# dc25-darknet-dialer-eaglev8_2.net
KiCad netlist of a schematic drawn in EAGLE
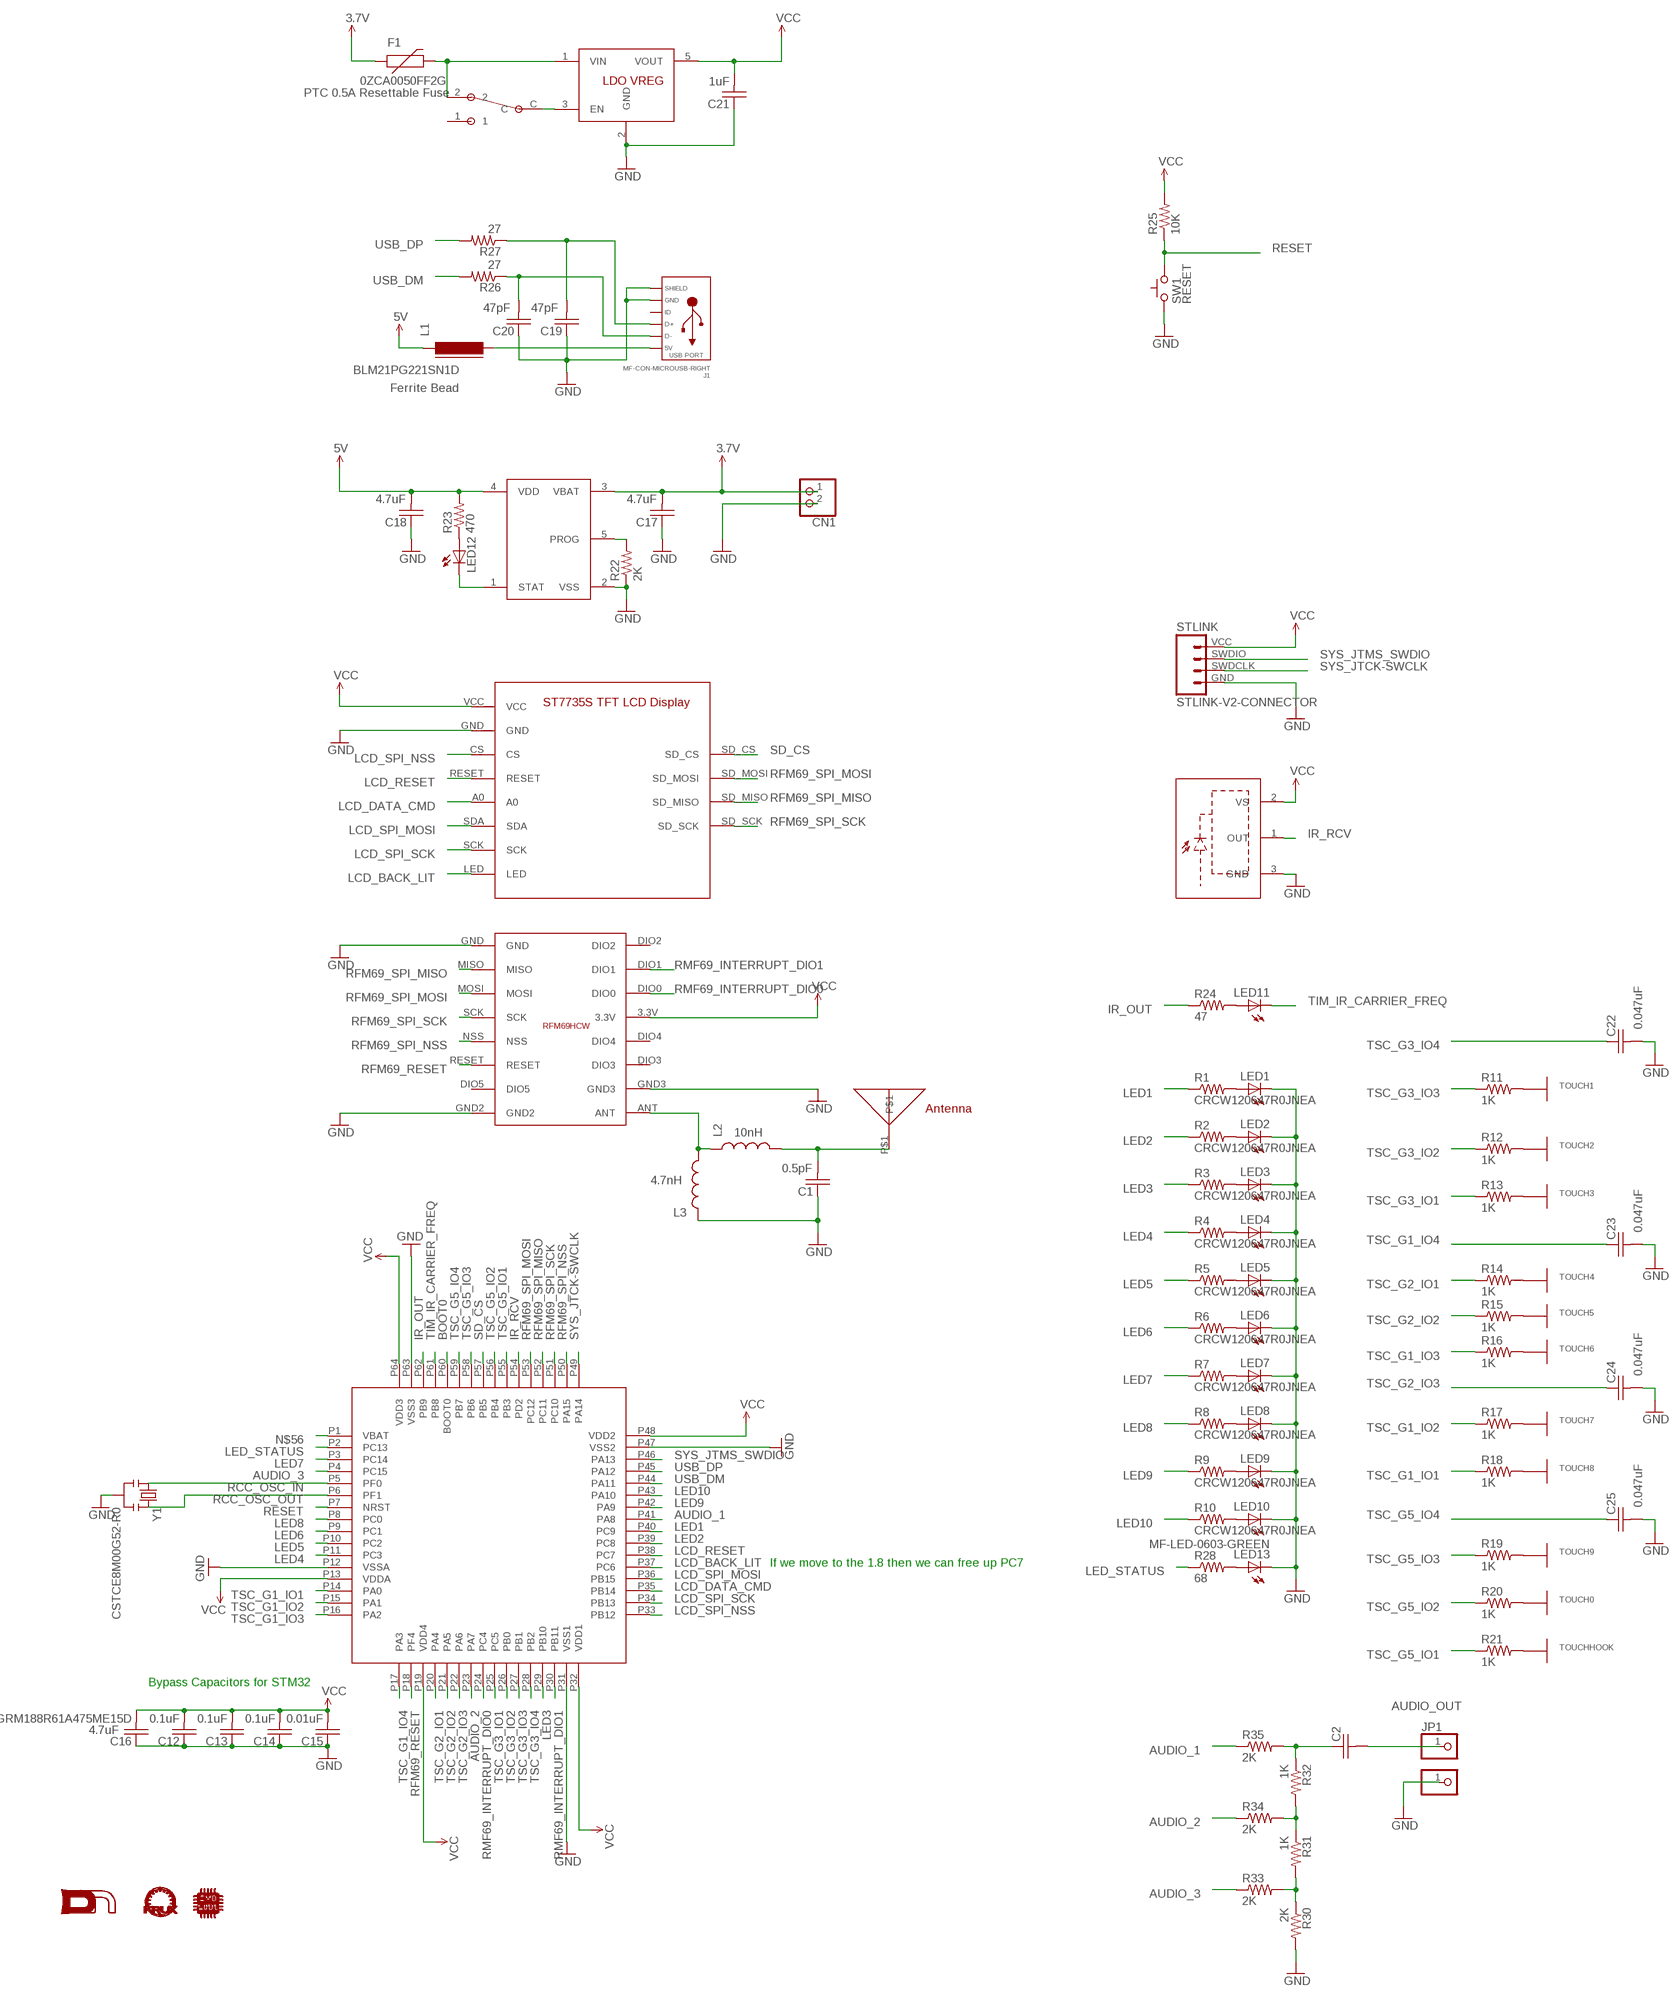
[diagram p0: schematic, sheet 1]

(export (version "E")
  (design (tool "Eeschema 10.0.6"))
  (components
    (comp (ref "C1")
      (value "251R14S0R5BV4T")
      (footprint "eagle-import:C0603")
      (libsource (lib "eagle-import") (part "C-USC0603"))
    )
    (comp (ref "C2")
      (value "GRM188C80G106ME47D")
      (footprint "eagle-import:C0603")
      (libsource (lib "eagle-import") (part "C-USC0603"))
    )
    (comp (ref "C12")
      (value "0.1uF")
      (footprint "eagle-import:C0603")
      (libsource (lib "eagle-import") (part "C-USC0603"))
    )
    (comp (ref "C13")
      (value "0.1uF")
      (footprint "eagle-import:C0603")
      (libsource (lib "eagle-import") (part "C-USC0603"))
    )
    (comp (ref "C14")
      (value "0.1uF")
      (footprint "eagle-import:C0603")
      (libsource (lib "eagle-import") (part "C-USC0603"))
    )
    (comp (ref "C15")
      (value "0.01uF")
      (footprint "eagle-import:C0603")
      (libsource (lib "eagle-import") (part "C-USC0603"))
    )
    (comp (ref "C16")
      (value "GRM188R61A475ME15D")
      (footprint "eagle-import:C0603")
      (libsource (lib "eagle-import") (part "C-USC0603"))
    )
    (comp (ref "C17")
      (value "GRM188R61A475ME15D")
      (footprint "eagle-import:C0603")
      (libsource (lib "eagle-import") (part "C-USC0603"))
    )
    (comp (ref "C18")
      (value "GRM188R61A475ME15D")
      (footprint "eagle-import:C0603")
      (libsource (lib "eagle-import") (part "C-USC0603"))
    )
    (comp (ref "C19")
      (value "C0603C470J3GACTU")
      (footprint "eagle-import:C0603")
      (libsource (lib "eagle-import") (part "C-USC0603"))
    )
    (comp (ref "C20")
      (value "C0603C470J3GACTU")
      (footprint "eagle-import:C0603")
      (libsource (lib "eagle-import") (part "C-USC0603"))
    )
    (comp (ref "C21")
      (value "1uF")
      (footprint "eagle-import:C0603")
      (libsource (lib "eagle-import") (part "C-USC0603"))
    )
    (comp (ref "C22")
      (value "C0603C473J3RACAUTO")
      (footprint "eagle-import:C0603")
      (libsource (lib "eagle-import") (part "C-USC0603"))
    )
    (comp (ref "C23")
      (value "C0603C473J3RACAUTO")
      (footprint "eagle-import:C0603")
      (libsource (lib "eagle-import") (part "C-USC0603"))
    )
    (comp (ref "C24")
      (value "C0603C473J3RACAUTO")
      (footprint "eagle-import:C0603")
      (libsource (lib "eagle-import") (part "C-USC0603"))
    )
    (comp (ref "C25")
      (value "C0603C473J3RACAUTO")
      (footprint "eagle-import:C0603")
      (libsource (lib "eagle-import") (part "C-USC0603"))
    )
    (comp (ref "CN1")
      (value "JST_2PIN-THM-RA")
      (footprint "eagle-import:JST-PH-2-THM-RA")
      (libsource (lib "eagle-import") (part "JST_2PIN-THM-RA"))
    )
    (comp (ref "F1")
      (value "0ZCA0050FF2G")
      (footprint "eagle-import:PTC-1206")
      (libsource (lib "eagle-import") (part "PTCSMD"))
    )
    (comp (ref "J1")
      (value "MF-CON-MICROUSB-RIGHT")
      (footprint "eagle-import:MICROUSB-RIGHT")
      (fields (field (name "HOUSEPART") "YES"))
      (libsource (lib "eagle-import") (part "USB_MICRO_RIGHT"))
    )
    (comp (ref "JP1")
      (value "PINHD-1X1CB")
      (footprint "eagle-import:1X01-CLEANBIG")
      (libsource (lib "eagle-import") (part "PINHD-1X1CB"))
    )
    (comp (ref "JP2")
      (value "PINHD-1X1CB")
      (footprint "eagle-import:1X01-CLEANBIG")
      (libsource (lib "eagle-import") (part "PINHD-1X1CB"))
    )
    (comp (ref "L1")
      (value "BLM21PG221SN1D")
      (footprint "eagle-import:FB603")
      (libsource (lib "eagle-import") (part "FERRITE-0603"))
    )
    (comp (ref "L2")
      (value "CI160808-10NJ")
      (footprint "eagle-import:0603")
      (libsource (lib "eagle-import") (part "INDUCTOR0603"))
    )
    (comp (ref "L3")
      (value "CI160808-4N7D")
      (footprint "eagle-import:0603")
      (libsource (lib "eagle-import") (part "INDUCTOR0603"))
    )
    (comp (ref "LED1")
      (value "LEDREVERSEMOUNT_NOPASTE")
      (footprint "eagle-import:GULLWING_LED_NOPASTE")
      (libsource (lib "eagle-import") (part "LEDREVERSEMOUNT_NOPASTE"))
    )
    (comp (ref "LED2")
      (value "LEDREVERSEMOUNT_NOPASTE")
      (footprint "eagle-import:GULLWING_LED_NOPASTE")
      (libsource (lib "eagle-import") (part "LEDREVERSEMOUNT_NOPASTE"))
    )
    (comp (ref "LED3")
      (value "LEDREVERSEMOUNT_NOPASTE")
      (footprint "eagle-import:GULLWING_LED_NOPASTE")
      (libsource (lib "eagle-import") (part "LEDREVERSEMOUNT_NOPASTE"))
    )
    (comp (ref "LED4")
      (value "LEDREVERSEMOUNT_NOPASTE")
      (footprint "eagle-import:GULLWING_LED_NOPASTE")
      (libsource (lib "eagle-import") (part "LEDREVERSEMOUNT_NOPASTE"))
    )
    (comp (ref "LED5")
      (value "LEDREVERSEMOUNT_NOPASTE")
      (footprint "eagle-import:GULLWING_LED_NOPASTE")
      (libsource (lib "eagle-import") (part "LEDREVERSEMOUNT_NOPASTE"))
    )
    (comp (ref "LED6")
      (value "LEDREVERSEMOUNT_NOPASTE")
      (footprint "eagle-import:GULLWING_LED_NOPASTE")
      (libsource (lib "eagle-import") (part "LEDREVERSEMOUNT_NOPASTE"))
    )
    (comp (ref "LED7")
      (value "LEDREVERSEMOUNT_NOPASTE")
      (footprint "eagle-import:GULLWING_LED_NOPASTE")
      (libsource (lib "eagle-import") (part "LEDREVERSEMOUNT_NOPASTE"))
    )
    (comp (ref "LED8")
      (value "LEDREVERSEMOUNT_NOPASTE")
      (footprint "eagle-import:GULLWING_LED_NOPASTE")
      (libsource (lib "eagle-import") (part "LEDREVERSEMOUNT_NOPASTE"))
    )
    (comp (ref "LED9")
      (value "LEDREVERSEMOUNT_NOPASTE")
      (footprint "eagle-import:GULLWING_LED_NOPASTE")
      (libsource (lib "eagle-import") (part "LEDREVERSEMOUNT_NOPASTE"))
    )
    (comp (ref "LED10")
      (value "LEDREVERSEMOUNT_NOPASTE")
      (footprint "eagle-import:GULLWING_LED_NOPASTE")
      (libsource (lib "eagle-import") (part "LEDREVERSEMOUNT_NOPASTE"))
    )
    (comp (ref "LED11")
      (value "LED5MM")
      (footprint "eagle-import:LED5MM")
      (libsource (lib "eagle-import") (part "LED5MM"))
    )
    (comp (ref "LED12")
      (value "MF-LED-0603-GREEN")
      (footprint "eagle-import:LED-0603")
      (libsource (lib "eagle-import") (part "LED0603"))
    )
    (comp (ref "LED13")
      (value "MF-LED-0603-GREEN")
      (footprint "eagle-import:LED-0603")
      (libsource (lib "eagle-import") (part "LED0603"))
    )
    (comp (ref "R1")
      (value "CRCW120647R0JNEA")
      (footprint "eagle-import:1206")
      (libsource (lib "eagle-import") (part "RESISTOR1206"))
    )
    (comp (ref "R2")
      (value "CRCW120647R0JNEA")
      (footprint "eagle-import:1206")
      (libsource (lib "eagle-import") (part "RESISTOR1206"))
    )
    (comp (ref "R3")
      (value "CRCW120647R0JNEA")
      (footprint "eagle-import:1206")
      (libsource (lib "eagle-import") (part "RESISTOR1206"))
    )
    (comp (ref "R4")
      (value "CRCW120647R0JNEA")
      (footprint "eagle-import:1206")
      (libsource (lib "eagle-import") (part "RESISTOR1206"))
    )
    (comp (ref "R5")
      (value "CRCW120647R0JNEA")
      (footprint "eagle-import:1206")
      (libsource (lib "eagle-import") (part "RESISTOR1206"))
    )
    (comp (ref "R6")
      (value "CRCW120647R0JNEA")
      (footprint "eagle-import:1206")
      (libsource (lib "eagle-import") (part "RESISTOR1206"))
    )
    (comp (ref "R7")
      (value "CRCW120647R0JNEA")
      (footprint "eagle-import:1206")
      (libsource (lib "eagle-import") (part "RESISTOR1206"))
    )
    (comp (ref "R8")
      (value "CRCW120647R0JNEA")
      (footprint "eagle-import:1206")
      (libsource (lib "eagle-import") (part "RESISTOR1206"))
    )
    (comp (ref "R9")
      (value "CRCW120647R0JNEA")
      (footprint "eagle-import:1206")
      (libsource (lib "eagle-import") (part "RESISTOR1206"))
    )
    (comp (ref "R10")
      (value "CRCW120647R0JNEA")
      (footprint "eagle-import:1206")
      (libsource (lib "eagle-import") (part "RESISTOR1206"))
    )
    (comp (ref "R11")
      (value "1K")
      (footprint "eagle-import:0603-RES")
      (libsource (lib "eagle-import") (part "RESISTOR0603-RES"))
    )
    (comp (ref "R12")
      (value "1K")
      (footprint "eagle-import:0603-RES")
      (libsource (lib "eagle-import") (part "RESISTOR0603-RES"))
    )
    (comp (ref "R13")
      (value "1K")
      (footprint "eagle-import:0603-RES")
      (libsource (lib "eagle-import") (part "RESISTOR0603-RES"))
    )
    (comp (ref "R14")
      (value "1K")
      (footprint "eagle-import:0603-RES")
      (libsource (lib "eagle-import") (part "RESISTOR0603-RES"))
    )
    (comp (ref "R15")
      (value "1K")
      (footprint "eagle-import:0603-RES")
      (libsource (lib "eagle-import") (part "RESISTOR0603-RES"))
    )
    (comp (ref "R16")
      (value "1K")
      (footprint "eagle-import:0603-RES")
      (libsource (lib "eagle-import") (part "RESISTOR0603-RES"))
    )
    (comp (ref "R17")
      (value "1K")
      (footprint "eagle-import:0603-RES")
      (libsource (lib "eagle-import") (part "RESISTOR0603-RES"))
    )
    (comp (ref "R18")
      (value "1K")
      (footprint "eagle-import:0603-RES")
      (libsource (lib "eagle-import") (part "RESISTOR0603-RES"))
    )
    (comp (ref "R19")
      (value "1K")
      (footprint "eagle-import:0603-RES")
      (libsource (lib "eagle-import") (part "RESISTOR0603-RES"))
    )
    (comp (ref "R20")
      (value "1K")
      (footprint "eagle-import:0603-RES")
      (libsource (lib "eagle-import") (part "RESISTOR0603-RES"))
    )
    (comp (ref "R21")
      (value "1K")
      (footprint "eagle-import:0603-RES")
      (libsource (lib "eagle-import") (part "RESISTOR0603-RES"))
    )
    (comp (ref "R22")
      (value "2K")
      (footprint "eagle-import:0603-RES")
      (libsource (lib "eagle-import") (part "RESISTOR0603-RES"))
    )
    (comp (ref "R23")
      (value "470")
      (footprint "eagle-import:0603-RES")
      (libsource (lib "eagle-import") (part "RESISTOR0603-RES"))
    )
    (comp (ref "R24")
      (value "47")
      (footprint "eagle-import:0207_7")
      (libsource (lib "eagle-import") (part "R-US_0207/7"))
    )
    (comp (ref "R25")
      (value "10K")
      (footprint "eagle-import:0603-RES")
      (libsource (lib "eagle-import") (part "RESISTOR0603-RES"))
    )
    (comp (ref "R26")
      (value "27")
      (footprint "eagle-import:0603-RES")
      (libsource (lib "eagle-import") (part "RESISTOR0603-RES"))
    )
    (comp (ref "R27")
      (value "27")
      (footprint "eagle-import:0603-RES")
      (libsource (lib "eagle-import") (part "RESISTOR0603-RES"))
    )
    (comp (ref "R28")
      (value "68")
      (footprint "eagle-import:0603-RES")
      (libsource (lib "eagle-import") (part "RESISTOR0603-RES"))
    )
    (comp (ref "R30")
      (value "2K")
      (footprint "eagle-import:0603-RES")
      (libsource (lib "eagle-import") (part "RESISTOR0603-RES"))
    )
    (comp (ref "R31")
      (value "1K")
      (footprint "eagle-import:0603-RES")
      (libsource (lib "eagle-import") (part "RESISTOR0603-RES"))
    )
    (comp (ref "R32")
      (value "1K")
      (footprint "eagle-import:0603-RES")
      (libsource (lib "eagle-import") (part "RESISTOR0603-RES"))
    )
    (comp (ref "R33")
      (value "2K")
      (footprint "eagle-import:0603-RES")
      (libsource (lib "eagle-import") (part "RESISTOR0603-RES"))
    )
    (comp (ref "R34")
      (value "2K")
      (footprint "eagle-import:0603-RES")
      (libsource (lib "eagle-import") (part "RESISTOR0603-RES"))
    )
    (comp (ref "R35")
      (value "2K")
      (footprint "eagle-import:0603-RES")
      (libsource (lib "eagle-import") (part "RESISTOR0603-RES"))
    )
    (comp (ref "STLINK")
      (value "STLINK-V2-CONNECTOR")
      (footprint "eagle-import:1X04")
      (libsource (lib "eagle-import") (part "STLINK-V2-CONNECTOR"))
    )
    (comp (ref "SW1")
      (value "RESET")
      (footprint "eagle-import:TACTILE-2PIN-NARROW")
      (libsource (lib "eagle-import") (part "SWITCH_TACTILETACTILE-2PIN-NARROW"))
    )
    (comp (ref "TOUCH0")
      (value "CAP_TOUCH0")
      (footprint "eagle-import:CAP_TOUCH_PAD_0")
      (libsource (lib "eagle-import") (part "CAP_TOUCH0"))
    )
    (comp (ref "TOUCH1")
      (value "CAP_TOUCH1")
      (footprint "eagle-import:CAP_TOUCH_PAD_1")
      (libsource (lib "eagle-import") (part "CAP_TOUCH1"))
    )
    (comp (ref "TOUCH2")
      (value "CAP_TOUCH2")
      (footprint "eagle-import:CAP_TOUCH_PAD_2")
      (libsource (lib "eagle-import") (part "CAP_TOUCH2"))
    )
    (comp (ref "TOUCH3")
      (value "CAP_TOUCH3")
      (footprint "eagle-import:CAP_TOUCH_PAD_3")
      (libsource (lib "eagle-import") (part "CAP_TOUCH3"))
    )
    (comp (ref "TOUCH4")
      (value "CAP_TOUCH4")
      (footprint "eagle-import:CAP_TOUCH_PAD_4")
      (libsource (lib "eagle-import") (part "CAP_TOUCH4"))
    )
    (comp (ref "TOUCH5")
      (value "CAP_TOUCH5")
      (footprint "eagle-import:CAP_TOUCH_PAD_5")
      (libsource (lib "eagle-import") (part "CAP_TOUCH5"))
    )
    (comp (ref "TOUCH6")
      (value "CAP_TOUCH6")
      (footprint "eagle-import:CAP_TOUCH_PAD_6")
      (libsource (lib "eagle-import") (part "CAP_TOUCH6"))
    )
    (comp (ref "TOUCH7")
      (value "CAP_TOUCH7")
      (footprint "eagle-import:CAP_TOUCH_PAD_7")
      (libsource (lib "eagle-import") (part "CAP_TOUCH7"))
    )
    (comp (ref "TOUCH8")
      (value "CAP_TOUCH8")
      (footprint "eagle-import:CAP_TOUCH_PAD_8")
      (libsource (lib "eagle-import") (part "CAP_TOUCH8"))
    )
    (comp (ref "TOUCH9")
      (value "CAP_TOUCH9")
      (footprint "eagle-import:CAP_TOUCH_PAD_9")
      (libsource (lib "eagle-import") (part "CAP_TOUCH9"))
    )
    (comp (ref "TOUCHHOOK")
      (value "CAP_TOUCHHOOK")
      (footprint "eagle-import:CAP_TOUCH_PAD_HOOK")
      (libsource (lib "eagle-import") (part "CAP_TOUCHHOOK"))
    )
    (comp (ref "U$1")
      (value "DN_LOGODC25")
      (footprint "eagle-import:DARKNET_LOGO_DC25")
      (libsource (lib "eagle-import") (part "DN_LOGODC25"))
    )
    (comp (ref "U$2")
      (value "STM32F302RBT6")
      (footprint "eagle-import:LQFP64")
      (libsource (lib "eagle-import") (part "STM32F302XC"))
    )
    (comp (ref "U$11")
      (value "SWITCH_SPDT")
      (footprint "eagle-import:SPDT_SSAJ120100")
      (libsource (lib "eagle-import") (part "SWITCH_SPDT"))
    )
    (comp (ref "U$12")
      (value "KRUX_LOGO")
      (footprint "eagle-import:KRUX_LOGO")
      (libsource (lib "eagle-import") (part "KRUX_LOGO"))
    )
    (comp (ref "U$15")
      (value "RFM69HCWRFM69HCWSMDNOPASTE")
      (footprint "eagle-import:16PIN-PCB-SMD-NOPASTE")
      (libsource (lib "eagle-import") (part "RFM69HCWRFM69HCWSMDNOPASTE"))
    )
    (comp (ref "U$21")
      (value "0915AT43A0026E")
      (footprint "eagle-import:CHIP_ANTENNA_1.8X8MM")
      (libsource (lib "eagle-import") (part "CHIP_ANTENNA"))
    )
    (comp (ref "U$22")
      (value "ST7735S_LCD_MODULE")
      (footprint "eagle-import:ST7735S_LCD_DISPLAY")
      (libsource (lib "eagle-import") (part "ST7735S_LCD_MODULE"))
    )
    (comp (ref "U$23")
      (value "CMD_C0DE_LOGO")
      (footprint "eagle-import:CMD_C0DE_LOGO")
      (libsource (lib "eagle-import") (part "CMD_C0DE_LOGO"))
    )
    (comp (ref "U1")
      (value "BU33SD5WG-TR")
      (footprint "eagle-import:SOT23-5")
      (libsource (lib "eagle-import") (part "TLV702"))
    )
    (comp (ref "U2")
      (value "MCP73831T-5ACI/OT")
      (footprint "eagle-import:SOT23-5")
      (libsource (lib "eagle-import") (part "DS21984E"))
    )
    (comp (ref "U3")
      (value "SOP22FLAT")
      (footprint "eagle-import:IR-MODULE_FLAT")
      (libsource (lib "eagle-import") (part "SOP22FLAT"))
    )
    (comp (ref "Y1")
      (value "CSTCE8M00G52-R0")
      (footprint "eagle-import:RESONATOR-SMD")
      (libsource (lib "eagle-import") (part "RESONATORSMD"))
    )
  )
  (nets
    (net (code "1") (name "/AUDIO_1") (class "Default")
      (node (ref "R35") (pin "1") (pinfunction "1_1") (pintype "passive"))
      (node (ref "U$2") (pin "P41") (pinfunction "PA8_P41") (pintype "bidirectional"))
    )
    (net (code "2") (name "/AUDIO_2") (class "Default")
      (node (ref "R34") (pin "1") (pinfunction "1_1") (pintype "passive"))
      (node (ref "U$2") (pin "P23") (pinfunction "PA7_P23") (pintype "bidirectional"))
    )
    (net (code "3") (name "/AUDIO_3") (class "Default")
      (node (ref "R33") (pin "1") (pinfunction "1_1") (pintype "passive"))
      (node (ref "U$2") (pin "P4") (pinfunction "PC15_P4") (pintype "bidirectional"))
    )
    (net (code "4") (name "/AUDIO_OUT") (class "Default")
      (node (ref "C2") (pin "2") (pinfunction "2_2") (pintype "passive"))
      (node (ref "JP1") (pin "1") (pinfunction "1_1") (pintype "passive"))
    )
    (net (code "5") (name "/BOOT0") (class "Default")
      (node (ref "U$2") (pin "P60") (pinfunction "BOOT0_P60") (pintype "bidirectional"))
    )
    (net (code "6") (name "/IR_OUT") (class "Default")
      (node (ref "R24") (pin "1") (pinfunction "1_1") (pintype "passive"))
      (node (ref "U$2") (pin "P62") (pinfunction "PB9_P62") (pintype "bidirectional"))
    )
    (net (code "7") (name "/IR_RCV") (class "Default")
      (node (ref "U$2") (pin "P54") (pinfunction "PD2_P54") (pintype "bidirectional"))
      (node (ref "U3") (pin "1") (pinfunction "OUT_1") (pintype "bidirectional"))
    )
    (net (code "8") (name "/LCD_BACK_LIT") (class "Default")
      (node (ref "U$2") (pin "P37") (pinfunction "PC6_P37") (pintype "bidirectional"))
      (node (ref "U$22") (pin "LED") (pinfunction "LED_LED") (pintype "bidirectional"))
    )
    (net (code "9") (name "/LCD_DATA_CMD") (class "Default")
      (node (ref "U$2") (pin "P35") (pinfunction "PB14_P35") (pintype "bidirectional"))
      (node (ref "U$22") (pin "A0") (pinfunction "A0_A0") (pintype "bidirectional"))
    )
    (net (code "10") (name "/LCD_RESET") (class "Default")
      (node (ref "U$2") (pin "P38") (pinfunction "PC7_P38") (pintype "bidirectional"))
      (node (ref "U$22") (pin "RESET") (pinfunction "RESET_RESET") (pintype "bidirectional"))
    )
    (net (code "11") (name "/LCD_SPI_MOSI") (class "Default")
      (node (ref "U$2") (pin "P36") (pinfunction "PB15_P36") (pintype "bidirectional"))
      (node (ref "U$22") (pin "SDA") (pinfunction "SDA_SDA") (pintype "bidirectional"))
    )
    (net (code "12") (name "/LCD_SPI_NSS") (class "Default")
      (node (ref "U$2") (pin "P33") (pinfunction "PB12_P33") (pintype "bidirectional"))
      (node (ref "U$22") (pin "CS") (pinfunction "CS_CS") (pintype "bidirectional"))
    )
    (net (code "13") (name "/LCD_SPI_SCK") (class "Default")
      (node (ref "U$2") (pin "P34") (pinfunction "PB13_P34") (pintype "bidirectional"))
      (node (ref "U$22") (pin "SCK") (pinfunction "SCK_SCK") (pintype "bidirectional"))
    )
    (net (code "14") (name "/LED1") (class "Default")
      (node (ref "R1") (pin "1") (pinfunction "1_1") (pintype "passive"))
      (node (ref "U$2") (pin "P40") (pinfunction "PC9_P40") (pintype "bidirectional"))
    )
    (net (code "15") (name "/LED2") (class "Default")
      (node (ref "R2") (pin "1") (pinfunction "1_1") (pintype "passive"))
      (node (ref "U$2") (pin "P39") (pinfunction "PC8_P39") (pintype "bidirectional"))
    )
    (net (code "16") (name "/LED3") (class "Default")
      (node (ref "R3") (pin "1") (pinfunction "1_1") (pintype "passive"))
      (node (ref "U$2") (pin "P29") (pinfunction "PB10_P29") (pintype "bidirectional"))
    )
    (net (code "17") (name "/LED4") (class "Default")
      (node (ref "R4") (pin "1") (pinfunction "1_1") (pintype "passive"))
      (node (ref "U$2") (pin "P11") (pinfunction "PC3_P11") (pintype "bidirectional"))
    )
    (net (code "18") (name "/LED5") (class "Default")
      (node (ref "R5") (pin "1") (pinfunction "1_1") (pintype "passive"))
      (node (ref "U$2") (pin "P10") (pinfunction "PC2_P10") (pintype "bidirectional"))
    )
    (net (code "19") (name "/LED6") (class "Default")
      (node (ref "R6") (pin "1") (pinfunction "1_1") (pintype "passive"))
      (node (ref "U$2") (pin "P9") (pinfunction "PC1_P9") (pintype "bidirectional"))
    )
    (net (code "20") (name "/LED7") (class "Default")
      (node (ref "R7") (pin "1") (pinfunction "1_1") (pintype "passive"))
      (node (ref "U$2") (pin "P3") (pinfunction "PC14_P3") (pintype "bidirectional"))
    )
    (net (code "21") (name "/LED8") (class "Default")
      (node (ref "R8") (pin "1") (pinfunction "1_1") (pintype "passive"))
      (node (ref "U$2") (pin "P8") (pinfunction "PC0_P8") (pintype "bidirectional"))
    )
    (net (code "22") (name "/LED9") (class "Default")
      (node (ref "R9") (pin "1") (pinfunction "1_1") (pintype "passive"))
      (node (ref "U$2") (pin "P42") (pinfunction "PA9_P42") (pintype "bidirectional"))
    )
    (net (code "23") (name "/LED10") (class "Default")
      (node (ref "R10") (pin "1") (pinfunction "1_1") (pintype "passive"))
      (node (ref "U$2") (pin "P43") (pinfunction "PA10_P43") (pintype "bidirectional"))
    )
    (net (code "24") (name "/LED_STATUS") (class "Default")
      (node (ref "R28") (pin "1") (pinfunction "1_1") (pintype "passive"))
      (node (ref "U$2") (pin "P2") (pinfunction "PC13_P2") (pintype "bidirectional"))
    )
    (net (code "25") (name "/N$56") (class "Default")
      (node (ref "U$2") (pin "P1") (pinfunction "VBAT_P1") (pintype "bidirectional"))
    )
    (net (code "26") (name "/RCC_OSC_IN") (class "Default")
      (node (ref "U$2") (pin "P5") (pinfunction "PF0_P5") (pintype "bidirectional"))
      (node (ref "Y1") (pin "1") (pinfunction "1_1") (pintype "passive"))
    )
    (net (code "27") (name "/RCC_OSC_OUT") (class "Default")
      (node (ref "U$2") (pin "P6") (pinfunction "PF1_P6") (pintype "bidirectional"))
      (node (ref "Y1") (pin "3") (pinfunction "3_3") (pintype "passive"))
    )
    (net (code "28") (name "/RESET") (class "Default")
      (node (ref "R25") (pin "1") (pinfunction "1_1") (pintype "passive"))
      (node (ref "SW1") (pin "P$1") (pinfunction "A_P$1") (pintype "passive"))
      (node (ref "U$2") (pin "P7") (pinfunction "NRST_P7") (pintype "bidirectional"))
    )
    (net (code "29") (name "/RFM69_RESET") (class "Default")
      (node (ref "U$15") (pin "RESET") (pinfunction "RESET_RESET") (pintype "bidirectional"))
      (node (ref "U$2") (pin "P18") (pinfunction "PF4_P18") (pintype "bidirectional"))
    )
    (net (code "30") (name "/RFM69_SPI_MISO") (class "Default")
      (node (ref "U$15") (pin "MISO") (pinfunction "MISO_MISO") (pintype "bidirectional"))
      (node (ref "U$2") (pin "P52") (pinfunction "PC11_P52") (pintype "bidirectional"))
      (node (ref "U$22") (pin "SD_MISO") (pinfunction "SD_MISO_SD_MISO") (pintype "bidirectional"))
    )
    (net (code "31") (name "/RFM69_SPI_MOSI") (class "Default")
      (node (ref "U$15") (pin "MOSI") (pinfunction "MOSI_MOSI") (pintype "bidirectional"))
      (node (ref "U$2") (pin "P53") (pinfunction "PC12_P53") (pintype "bidirectional"))
      (node (ref "U$22") (pin "SD_MOSI") (pinfunction "SD_MOSI_SD_MOSI") (pintype "bidirectional"))
    )
    (net (code "32") (name "/RFM69_SPI_NSS") (class "Default")
      (node (ref "U$15") (pin "NSS") (pinfunction "NSS_NSS") (pintype "bidirectional"))
      (node (ref "U$2") (pin "P50") (pinfunction "PA15_P50") (pintype "bidirectional"))
    )
    (net (code "33") (name "/RFM69_SPI_SCK") (class "Default")
      (node (ref "U$15") (pin "SCK") (pinfunction "SCK_SCK") (pintype "bidirectional"))
      (node (ref "U$2") (pin "P51") (pinfunction "PC10_P51") (pintype "bidirectional"))
      (node (ref "U$22") (pin "SD_SCK") (pinfunction "SD_SCK_SD_SCK") (pintype "bidirectional"))
    )
    (net (code "34") (name "/RMF69_INTERRUPT_DIO0") (class "Default")
      (node (ref "U$15") (pin "DIO0") (pinfunction "DIO0_DIO0") (pintype "bidirectional"))
      (node (ref "U$2") (pin "P24") (pinfunction "PC4_P24") (pintype "bidirectional"))
    )
    (net (code "35") (name "/RMF69_INTERRUPT_DIO1") (class "Default")
      (node (ref "U$15") (pin "DIO1") (pinfunction "DIO1_DIO1") (pintype "bidirectional"))
      (node (ref "U$2") (pin "P30") (pinfunction "PB11_P30") (pintype "bidirectional"))
    )
    (net (code "36") (name "/SD_CS") (class "Default")
      (node (ref "U$2") (pin "P57") (pinfunction "PB5_P57") (pintype "bidirectional"))
      (node (ref "U$22") (pin "SD_CS") (pinfunction "SD_CS_SD_CS") (pintype "bidirectional"))
    )
    (net (code "37") (name "/SYS_JTCK-SWCLK") (class "Default")
      (node (ref "STLINK") (pin "SWDCLK") (pinfunction "SWDCLK_SWDCLK") (pintype "input"))
      (node (ref "U$2") (pin "P49") (pinfunction "PA14_P49") (pintype "bidirectional"))
    )
    (net (code "38") (name "/SYS_JTMS_SWDIO") (class "Default")
      (node (ref "STLINK") (pin "SWDIO") (pinfunction "SWDIO_SWDIO") (pintype "bidirectional"))
      (node (ref "U$2") (pin "P46") (pinfunction "PA13_P46") (pintype "bidirectional"))
    )
    (net (code "39") (name "/TIM_IR_CARRIER_FREQ") (class "Default")
      (node (ref "LED11") (pin "K") (pinfunction "C_K") (pintype "output"))
      (node (ref "U$2") (pin "P61") (pinfunction "PB8_P61") (pintype "bidirectional"))
    )
    (net (code "40") (name "/TSC_G1_IO1") (class "Default")
      (node (ref "R18") (pin "1") (pinfunction "1_1") (pintype "passive"))
      (node (ref "U$2") (pin "P14") (pinfunction "PA0_P14") (pintype "bidirectional"))
    )
    (net (code "41") (name "/TSC_G1_IO2") (class "Default")
      (node (ref "R17") (pin "1") (pinfunction "1_1") (pintype "passive"))
      (node (ref "U$2") (pin "P15") (pinfunction "PA1_P15") (pintype "bidirectional"))
    )
    (net (code "42") (name "/TSC_G1_IO3") (class "Default")
      (node (ref "R16") (pin "1") (pinfunction "1_1") (pintype "passive"))
      (node (ref "U$2") (pin "P16") (pinfunction "PA2_P16") (pintype "bidirectional"))
    )
    (net (code "43") (name "/TSC_G1_IO4") (class "Default")
      (node (ref "C23") (pin "1") (pinfunction "1_1") (pintype "passive"))
      (node (ref "U$2") (pin "P17") (pinfunction "PA3_P17") (pintype "bidirectional"))
    )
    (net (code "44") (name "/TSC_G2_IO1") (class "Default")
      (node (ref "R14") (pin "1") (pinfunction "1_1") (pintype "passive"))
      (node (ref "U$2") (pin "P20") (pinfunction "PA4_P20") (pintype "bidirectional"))
    )
    (net (code "45") (name "/TSC_G2_IO2") (class "Default")
      (node (ref "R15") (pin "1") (pinfunction "1_1") (pintype "passive"))
      (node (ref "U$2") (pin "P21") (pinfunction "PA5_P21") (pintype "bidirectional"))
    )
    (net (code "46") (name "/TSC_G2_IO3") (class "Default")
      (node (ref "C24") (pin "1") (pinfunction "1_1") (pintype "passive"))
      (node (ref "U$2") (pin "P22") (pinfunction "PA6_P22") (pintype "bidirectional"))
    )
    (net (code "47") (name "/TSC_G3_IO1") (class "Default")
      (node (ref "R13") (pin "1") (pinfunction "1_1") (pintype "passive"))
      (node (ref "U$2") (pin "P25") (pinfunction "PC5_P25") (pintype "bidirectional"))
    )
    (net (code "48") (name "/TSC_G3_IO2") (class "Default")
      (node (ref "R12") (pin "1") (pinfunction "1_1") (pintype "passive"))
      (node (ref "U$2") (pin "P26") (pinfunction "PB0_P26") (pintype "bidirectional"))
    )
    (net (code "49") (name "/TSC_G3_IO3") (class "Default")
      (node (ref "R11") (pin "1") (pinfunction "1_1") (pintype "passive"))
      (node (ref "U$2") (pin "P27") (pinfunction "PB1_P27") (pintype "bidirectional"))
    )
    (net (code "50") (name "/TSC_G3_IO4") (class "Default")
      (node (ref "C22") (pin "1") (pinfunction "1_1") (pintype "passive"))
      (node (ref "U$2") (pin "P28") (pinfunction "PB2_P28") (pintype "bidirectional"))
    )
    (net (code "51") (name "/TSC_G5_IO1") (class "Default")
      (node (ref "R21") (pin "1") (pinfunction "1_1") (pintype "passive"))
      (node (ref "U$2") (pin "P55") (pinfunction "PB3_P55") (pintype "bidirectional"))
    )
    (net (code "52") (name "/TSC_G5_IO2") (class "Default")
      (node (ref "R20") (pin "1") (pinfunction "1_1") (pintype "passive"))
      (node (ref "U$2") (pin "P56") (pinfunction "PB4_P56") (pintype "bidirectional"))
    )
    (net (code "53") (name "/TSC_G5_IO3") (class "Default")
      (node (ref "R19") (pin "1") (pinfunction "1_1") (pintype "passive"))
      (node (ref "U$2") (pin "P58") (pinfunction "PB6_P58") (pintype "bidirectional"))
    )
    (net (code "54") (name "/TSC_G5_IO4") (class "Default")
      (node (ref "C25") (pin "1") (pinfunction "1_1") (pintype "passive"))
      (node (ref "U$2") (pin "P59") (pinfunction "PB7_P59") (pintype "bidirectional"))
    )
    (net (code "55") (name "/USB_DM") (class "Default")
      (node (ref "R26") (pin "2") (pinfunction "2_2") (pintype "passive"))
      (node (ref "U$2") (pin "P44") (pinfunction "PA11_P44") (pintype "bidirectional"))
    )
    (net (code "56") (name "/USB_DP") (class "Default")
      (node (ref "R27") (pin "2") (pinfunction "2_2") (pintype "passive"))
      (node (ref "U$2") (pin "P45") (pinfunction "PA12_P45") (pintype "bidirectional"))
    )
    (net (code "57") (name "3.7V") (class "Default")
      (node (ref "C17") (pin "2") (pinfunction "2_2") (pintype "passive"))
      (node (ref "CN1") (pin "1") (pinfunction "2_1") (pintype "passive"))
      (node (ref "F1") (pin "1") (pinfunction "1_1") (pintype "bidirectional"))
      (node (ref "U2") (pin "3") (pinfunction "VBAT_3") (pintype "bidirectional"))
    )
    (net (code "58") (name "5V") (class "Default")
      (node (ref "C18") (pin "2") (pinfunction "2_2") (pintype "passive"))
      (node (ref "L1") (pin "1") (pinfunction "1_1") (pintype "passive"))
      (node (ref "R23") (pin "2") (pinfunction "2_2") (pintype "passive"))
      (node (ref "U2") (pin "4") (pinfunction "VDD_4") (pintype "bidirectional"))
    )
    (net (code "59") (name "GND") (class "Default")
      (node (ref "C1") (pin "1") (pinfunction "1_1") (pintype "passive"))
      (node (ref "C12") (pin "1") (pinfunction "1_1") (pintype "passive"))
      (node (ref "C13") (pin "1") (pinfunction "1_1") (pintype "passive"))
      (node (ref "C14") (pin "1") (pinfunction "1_1") (pintype "passive"))
      (node (ref "C15") (pin "1") (pinfunction "1_1") (pintype "passive"))
      (node (ref "C16") (pin "1") (pinfunction "1_1") (pintype "passive"))
      (node (ref "C17") (pin "1") (pinfunction "1_1") (pintype "passive"))
      (node (ref "C18") (pin "1") (pinfunction "1_1") (pintype "passive"))
      (node (ref "C19") (pin "1") (pinfunction "1_1") (pintype "passive"))
      (node (ref "C20") (pin "1") (pinfunction "1_1") (pintype "passive"))
      (node (ref "C21") (pin "1") (pinfunction "1_1") (pintype "passive"))
      (node (ref "C22") (pin "2") (pinfunction "2_2") (pintype "passive"))
      (node (ref "C23") (pin "2") (pinfunction "2_2") (pintype "passive"))
      (node (ref "C24") (pin "2") (pinfunction "2_2") (pintype "passive"))
      (node (ref "C25") (pin "2") (pinfunction "2_2") (pintype "passive"))
      (node (ref "CN1") (pin "2") (pinfunction "1_2") (pintype "passive"))
      (node (ref "J1") (pin "5") (pinfunction "GND_5") (pintype "power_in"))
      (node (ref "J1") (pin "S1") (pinfunction "SLD_S1") (pintype "power_in"))
      (node (ref "J1") (pin "S2") (pinfunction "SLD_S2") (pintype "power_in"))
      (node (ref "J1") (pin "S3") (pinfunction "SLD_S3") (pintype "power_in"))
      (node (ref "J1") (pin "S4") (pinfunction "SLD_S4") (pintype "power_in"))
      (node (ref "J1") (pin "S5") (pinfunction "SLD_S5") (pintype "power_in"))
      (node (ref "J1") (pin "S6") (pinfunction "SLD_S6") (pintype "power_in"))
      (node (ref "JP2") (pin "1") (pinfunction "1_1") (pintype "passive"))
      (node (ref "L3") (pin "1") (pinfunction "1_1") (pintype "passive"))
      (node (ref "LED1") (pin "C") (pinfunction "C_C") (pintype "output"))
      (node (ref "LED10") (pin "C") (pinfunction "C_C") (pintype "output"))
      (node (ref "LED13") (pin "C") (pinfunction "C_C") (pintype "output"))
      (node (ref "LED2") (pin "C") (pinfunction "C_C") (pintype "output"))
      (node (ref "LED3") (pin "C") (pinfunction "C_C") (pintype "output"))
      (node (ref "LED4") (pin "C") (pinfunction "C_C") (pintype "output"))
      (node (ref "LED5") (pin "C") (pinfunction "C_C") (pintype "output"))
      (node (ref "LED6") (pin "C") (pinfunction "C_C") (pintype "output"))
      (node (ref "LED7") (pin "C") (pinfunction "C_C") (pintype "output"))
      (node (ref "LED8") (pin "C") (pinfunction "C_C") (pintype "output"))
      (node (ref "LED9") (pin "C") (pinfunction "C_C") (pintype "output"))
      (node (ref "R22") (pin "1") (pinfunction "1_1") (pintype "passive"))
      (node (ref "R30") (pin "2") (pinfunction "2_2") (pintype "passive"))
      (node (ref "STLINK") (pin "GND") (pinfunction "GND_GND") (pintype "power_in"))
      (node (ref "SW1") (pin "P$2") (pinfunction "C_P$2") (pintype "passive"))
      (node (ref "U$15") (pin "GND") (pinfunction "GND_GND") (pintype "bidirectional"))
      (node (ref "U$15") (pin "GND2") (pinfunction "GND2_GND2") (pintype "bidirectional"))
      (node (ref "U$15") (pin "GND3") (pinfunction "GND3_GND3") (pintype "bidirectional"))
      (node (ref "U$2") (pin "P12") (pinfunction "VSSA_P12") (pintype "bidirectional"))
      (node (ref "U$2") (pin "P31") (pinfunction "VSS1_P31") (pintype "bidirectional"))
      (node (ref "U$2") (pin "P47") (pinfunction "VSS2_P47") (pintype "bidirectional"))
      (node (ref "U$2") (pin "P63") (pinfunction "VSS3_P63") (pintype "bidirectional"))
      (node (ref "U$22") (pin "GND") (pinfunction "GND_GND") (pintype "bidirectional"))
      (node (ref "U1") (pin "2") (pinfunction "GND_2") (pintype "bidirectional"))
      (node (ref "U2") (pin "2") (pinfunction "VSS_2") (pintype "bidirectional"))
      (node (ref "U3") (pin "3") (pinfunction "GND_3") (pintype "bidirectional"))
      (node (ref "Y1") (pin "2") (pinfunction "2_2") (pintype "passive"))
    )
    (net (code "60") (name "Net-(C1-Pad2)") (class "Default")
      (node (ref "C1") (pin "2") (pinfunction "2_2") (pintype "passive"))
      (node (ref "L2") (pin "2") (pinfunction "2_2") (pintype "passive"))
      (node (ref "U$21") (pin "P$1") (pinfunction "P$1_P$1") (pintype "bidirectional"))
    )
    (net (code "61") (name "Net-(C2-Pad1)") (class "Default")
      (node (ref "C2") (pin "1") (pinfunction "1_1") (pintype "passive"))
      (node (ref "R32") (pin "1") (pinfunction "1_1") (pintype "passive"))
      (node (ref "R35") (pin "2") (pinfunction "2_2") (pintype "passive"))
    )
    (net (code "62") (name "Net-(J1-5V)") (class "Default")
      (node (ref "J1") (pin "1") (pinfunction "5V_1") (pintype "power_in"))
      (node (ref "L1") (pin "2") (pinfunction "2_2") (pintype "passive"))
    )
    (net (code "63") (name "Net-(J1-D+)") (class "Default")
      (node (ref "C19") (pin "2") (pinfunction "2_2") (pintype "passive"))
      (node (ref "J1") (pin "3") (pinfunction "D+_3") (pintype "bidirectional"))
      (node (ref "R27") (pin "1") (pinfunction "1_1") (pintype "passive"))
    )
    (net (code "64") (name "Net-(J1-D-)") (class "Default")
      (node (ref "C20") (pin "2") (pinfunction "2_2") (pintype "passive"))
      (node (ref "J1") (pin "2") (pinfunction "D-_2") (pintype "bidirectional"))
      (node (ref "R26") (pin "1") (pinfunction "1_1") (pintype "passive"))
    )
    (net (code "65") (name "Net-(L2-Pad1)") (class "Default")
      (node (ref "L2") (pin "1") (pinfunction "1_1") (pintype "passive"))
      (node (ref "L3") (pin "2") (pinfunction "2_2") (pintype "passive"))
      (node (ref "U$15") (pin "ANT") (pinfunction "ANT_ANT") (pintype "bidirectional"))
    )
    (net (code "66") (name "Net-(LED1-PadA)") (class "Default")
      (node (ref "LED1") (pin "A") (pinfunction "A_A") (pintype "input"))
      (node (ref "R1") (pin "2") (pinfunction "2_2") (pintype "passive"))
    )
    (net (code "67") (name "Net-(LED2-PadA)") (class "Default")
      (node (ref "LED2") (pin "A") (pinfunction "A_A") (pintype "input"))
      (node (ref "R2") (pin "2") (pinfunction "2_2") (pintype "passive"))
    )
    (net (code "68") (name "Net-(LED3-PadA)") (class "Default")
      (node (ref "LED3") (pin "A") (pinfunction "A_A") (pintype "input"))
      (node (ref "R3") (pin "2") (pinfunction "2_2") (pintype "passive"))
    )
    (net (code "69") (name "Net-(LED4-PadA)") (class "Default")
      (node (ref "LED4") (pin "A") (pinfunction "A_A") (pintype "input"))
      (node (ref "R4") (pin "2") (pinfunction "2_2") (pintype "passive"))
    )
    (net (code "70") (name "Net-(LED5-PadA)") (class "Default")
      (node (ref "LED5") (pin "A") (pinfunction "A_A") (pintype "input"))
      (node (ref "R5") (pin "2") (pinfunction "2_2") (pintype "passive"))
    )
    (net (code "71") (name "Net-(LED6-PadA)") (class "Default")
      (node (ref "LED6") (pin "A") (pinfunction "A_A") (pintype "input"))
      (node (ref "R6") (pin "2") (pinfunction "2_2") (pintype "passive"))
    )
    (net (code "72") (name "Net-(LED7-PadA)") (class "Default")
      (node (ref "LED7") (pin "A") (pinfunction "A_A") (pintype "input"))
      (node (ref "R7") (pin "2") (pinfunction "2_2") (pintype "passive"))
    )
    (net (code "73") (name "Net-(LED8-PadA)") (class "Default")
      (node (ref "LED8") (pin "A") (pinfunction "A_A") (pintype "input"))
      (node (ref "R8") (pin "2") (pinfunction "2_2") (pintype "passive"))
    )
    (net (code "74") (name "Net-(LED9-PadA)") (class "Default")
      (node (ref "LED9") (pin "A") (pinfunction "A_A") (pintype "input"))
      (node (ref "R9") (pin "2") (pinfunction "2_2") (pintype "passive"))
    )
    (net (code "75") (name "Net-(LED10-PadA)") (class "Default")
      (node (ref "LED10") (pin "A") (pinfunction "A_A") (pintype "input"))
      (node (ref "R10") (pin "2") (pinfunction "2_2") (pintype "passive"))
    )
    (net (code "76") (name "Net-(LED11-PadA)") (class "Default")
      (node (ref "LED11") (pin "A") (pinfunction "A_A") (pintype "input"))
      (node (ref "R24") (pin "2") (pinfunction "2_2") (pintype "passive"))
    )
    (net (code "77") (name "Net-(LED12-PadA)") (class "Default")
      (node (ref "LED12") (pin "A") (pinfunction "A_A") (pintype "input"))
      (node (ref "R23") (pin "1") (pinfunction "1_1") (pintype "passive"))
    )
    (net (code "78") (name "Net-(LED13-PadA)") (class "Default")
      (node (ref "LED13") (pin "A") (pinfunction "A_A") (pintype "input"))
      (node (ref "R28") (pin "2") (pinfunction "2_2") (pintype "passive"))
    )
    (net (code "79") (name "Net-(R30-Pad1)") (class "Default")
      (node (ref "R30") (pin "1") (pinfunction "1_1") (pintype "passive"))
      (node (ref "R31") (pin "2") (pinfunction "2_2") (pintype "passive"))
      (node (ref "R33") (pin "2") (pinfunction "2_2") (pintype "passive"))
    )
    (net (code "80") (name "Net-(R31-Pad1)") (class "Default")
      (node (ref "R31") (pin "1") (pinfunction "1_1") (pintype "passive"))
      (node (ref "R32") (pin "2") (pinfunction "2_2") (pintype "passive"))
      (node (ref "R34") (pin "2") (pinfunction "2_2") (pintype "passive"))
    )
    (net (code "81") (name "Net-(TOUCH0-TOUCH)") (class "Default")
      (node (ref "R20") (pin "2") (pinfunction "2_2") (pintype "passive"))
      (node (ref "TOUCH0") (pin "PAD") (pinfunction "TOUCH_PAD") (pintype "bidirectional"))
    )
    (net (code "82") (name "Net-(TOUCH1-TOUCH)") (class "Default")
      (node (ref "R11") (pin "2") (pinfunction "2_2") (pintype "passive"))
      (node (ref "TOUCH1") (pin "PAD") (pinfunction "TOUCH_PAD") (pintype "bidirectional"))
    )
    (net (code "83") (name "Net-(TOUCH2-TOUCH)") (class "Default")
      (node (ref "R12") (pin "2") (pinfunction "2_2") (pintype "passive"))
      (node (ref "TOUCH2") (pin "PAD") (pinfunction "TOUCH_PAD") (pintype "bidirectional"))
    )
    (net (code "84") (name "Net-(TOUCH3-TOUCH)") (class "Default")
      (node (ref "R13") (pin "2") (pinfunction "2_2") (pintype "passive"))
      (node (ref "TOUCH3") (pin "PAD") (pinfunction "TOUCH_PAD") (pintype "bidirectional"))
    )
    (net (code "85") (name "Net-(TOUCH4-TOUCH)") (class "Default")
      (node (ref "R14") (pin "2") (pinfunction "2_2") (pintype "passive"))
      (node (ref "TOUCH4") (pin "PAD") (pinfunction "TOUCH_PAD") (pintype "bidirectional"))
    )
    (net (code "86") (name "Net-(TOUCH5-TOUCH)") (class "Default")
      (node (ref "R15") (pin "2") (pinfunction "2_2") (pintype "passive"))
      (node (ref "TOUCH5") (pin "PAD") (pinfunction "TOUCH_PAD") (pintype "bidirectional"))
    )
    (net (code "87") (name "Net-(TOUCH6-TOUCH)") (class "Default")
      (node (ref "R16") (pin "2") (pinfunction "2_2") (pintype "passive"))
      (node (ref "TOUCH6") (pin "PAD") (pinfunction "TOUCH_PAD") (pintype "bidirectional"))
    )
    (net (code "88") (name "Net-(TOUCH7-TOUCH)") (class "Default")
      (node (ref "R17") (pin "2") (pinfunction "2_2") (pintype "passive"))
      (node (ref "TOUCH7") (pin "PAD") (pinfunction "TOUCH_PAD") (pintype "bidirectional"))
    )
    (net (code "89") (name "Net-(TOUCH8-TOUCH)") (class "Default")
      (node (ref "R18") (pin "2") (pinfunction "2_2") (pintype "passive"))
      (node (ref "TOUCH8") (pin "PAD") (pinfunction "TOUCH_PAD") (pintype "bidirectional"))
    )
    (net (code "90") (name "Net-(TOUCH9-TOUCH)") (class "Default")
      (node (ref "R19") (pin "2") (pinfunction "2_2") (pintype "passive"))
      (node (ref "TOUCH9") (pin "PAD") (pinfunction "TOUCH_PAD") (pintype "bidirectional"))
    )
    (net (code "91") (name "Net-(TOUCHHOOK-TOUCH)") (class "Default")
      (node (ref "R21") (pin "2") (pinfunction "2_2") (pintype "passive"))
      (node (ref "TOUCHHOOK") (pin "P$1") (pinfunction "TOUCH_P$1") (pintype "bidirectional"))
    )
    (net (code "92") (name "Net-(U1-EN)") (class "Default")
      (node (ref "U$11") (pin "C") (pinfunction "C_C") (pintype "bidirectional"))
      (node (ref "U1") (pin "3") (pinfunction "EN_3") (pintype "bidirectional"))
    )
    (net (code "93") (name "Net-(U1-VIN)") (class "Default")
      (node (ref "F1") (pin "2") (pinfunction "2_2") (pintype "bidirectional"))
      (node (ref "U$11") (pin "2") (pinfunction "2_2") (pintype "bidirectional"))
      (node (ref "U1") (pin "1") (pinfunction "VIN_1") (pintype "bidirectional"))
    )
    (net (code "94") (name "Net-(U2-PROG)") (class "Default")
      (node (ref "R22") (pin "2") (pinfunction "2_2") (pintype "passive"))
      (node (ref "U2") (pin "5") (pinfunction "PROG_5") (pintype "bidirectional"))
    )
    (net (code "95") (name "Net-(U2-STAT)") (class "Default")
      (node (ref "LED12") (pin "C") (pinfunction "C_C") (pintype "output"))
      (node (ref "U2") (pin "1") (pinfunction "STAT_1") (pintype "bidirectional"))
    )
    (net (code "96") (name "VCC") (class "Default")
      (node (ref "C12") (pin "2") (pinfunction "2_2") (pintype "passive"))
      (node (ref "C13") (pin "2") (pinfunction "2_2") (pintype "passive"))
      (node (ref "C14") (pin "2") (pinfunction "2_2") (pintype "passive"))
      (node (ref "C15") (pin "2") (pinfunction "2_2") (pintype "passive"))
      (node (ref "C16") (pin "2") (pinfunction "2_2") (pintype "passive"))
      (node (ref "C21") (pin "2") (pinfunction "2_2") (pintype "passive"))
      (node (ref "R25") (pin "2") (pinfunction "2_2") (pintype "passive"))
      (node (ref "STLINK") (pin "VCC") (pinfunction "VCC_VCC") (pintype "power_in"))
      (node (ref "U$15") (pin "3.3V") (pinfunction "3.3V_3.3V") (pintype "bidirectional"))
      (node (ref "U$2") (pin "P13") (pinfunction "VDDA_P13") (pintype "bidirectional"))
      (node (ref "U$2") (pin "P19") (pinfunction "VDD4_P19") (pintype "bidirectional"))
      (node (ref "U$2") (pin "P32") (pinfunction "VDD1_P32") (pintype "bidirectional"))
      (node (ref "U$2") (pin "P48") (pinfunction "VDD2_P48") (pintype "bidirectional"))
      (node (ref "U$2") (pin "P64") (pinfunction "VDD3_P64") (pintype "bidirectional"))
      (node (ref "U$22") (pin "VCC") (pinfunction "VCC_VCC") (pintype "bidirectional"))
      (node (ref "U1") (pin "5") (pinfunction "VOUT_5") (pintype "bidirectional"))
      (node (ref "U3") (pin "2") (pinfunction "VS_2") (pintype "bidirectional"))
    )
    (net (code "97") (name "unconnected-(J1-ID-Pad4)") (class "Default")
      (node (ref "J1") (pin "4") (pinfunction "ID_4") (pintype "bidirectional"))
    )
    (net (code "98") (name "unconnected-(U$11-Pad1)") (class "Default")
      (node (ref "U$11") (pin "1") (pinfunction "1_1") (pintype "bidirectional"))
    )
    (net (code "99") (name "unconnected-(U$15-PadDIO2)") (class "Default")
      (node (ref "U$15") (pin "DIO2") (pinfunction "DIO2_DIO2") (pintype "bidirectional"))
    )
    (net (code "100") (name "unconnected-(U$15-PadDIO3)") (class "Default")
      (node (ref "U$15") (pin "DIO3") (pinfunction "DIO3_DIO3") (pintype "bidirectional"))
    )
    (net (code "101") (name "unconnected-(U$15-PadDIO4)") (class "Default")
      (node (ref "U$15") (pin "DIO4") (pinfunction "DIO4_DIO4") (pintype "bidirectional"))
    )
    (net (code "102") (name "unconnected-(U$15-PadDIO5)") (class "Default")
      (node (ref "U$15") (pin "DIO5") (pinfunction "DIO5_DIO5") (pintype "bidirectional"))
    )
  )
)
